# main.net
KiCad netlist of a schematic drawn in EAGLE
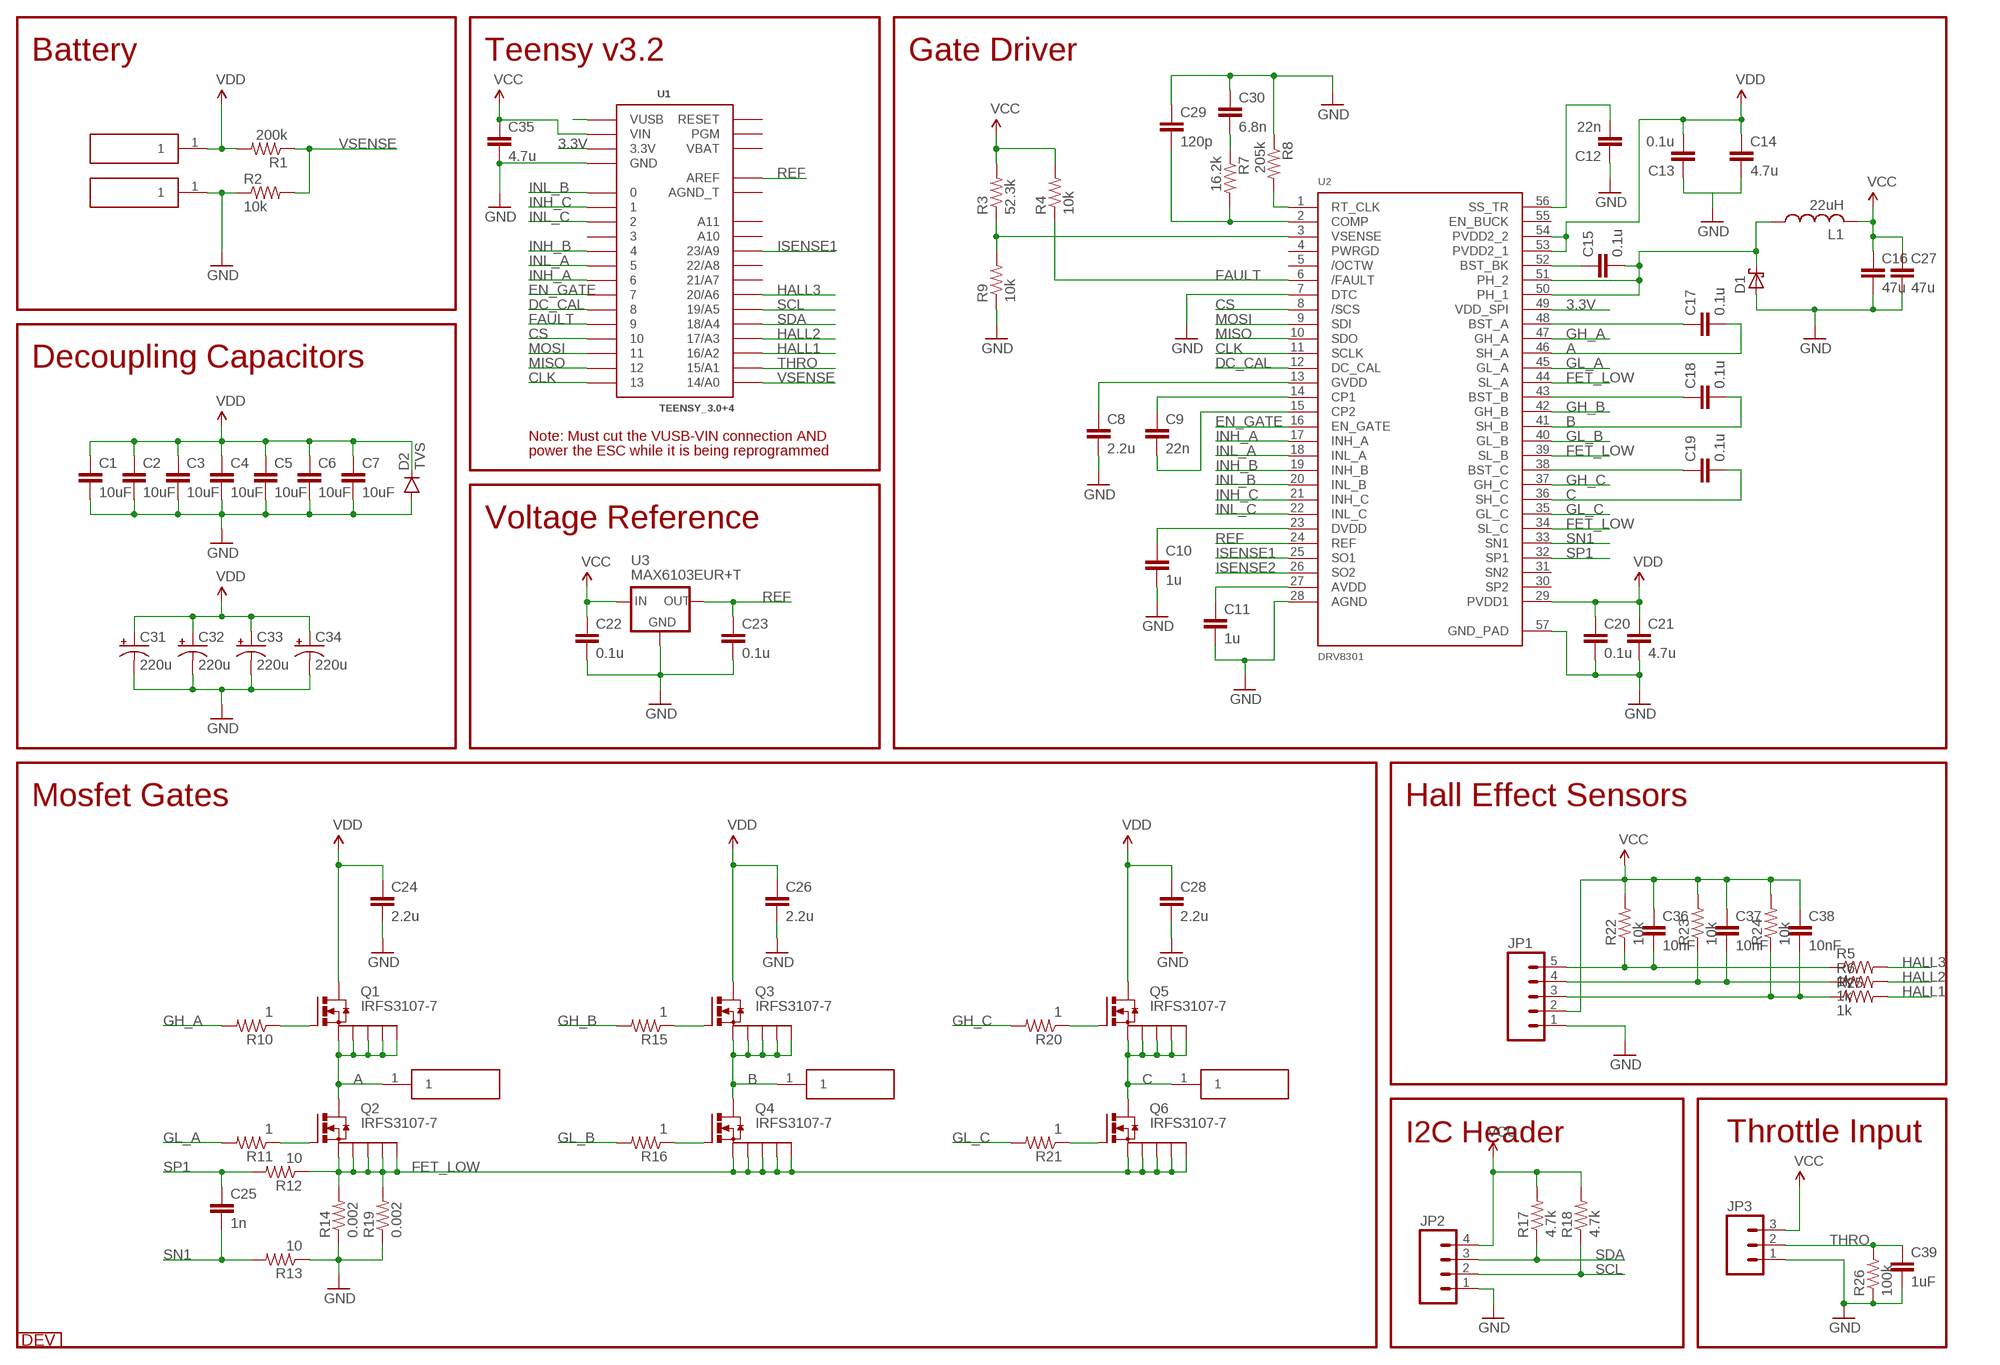
[diagram p0: schematic, sheet 1]

(export (version "E")
  (design (tool "Eeschema 10.0.6"))
  (components
    (comp (ref "C1")
      (value "10uF")
      (footprint "eagle-import:1206")
      (libsource (lib "eagle-import") (part "CAP1206"))
    )
    (comp (ref "C2")
      (value "10uF")
      (footprint "eagle-import:1206")
      (libsource (lib "eagle-import") (part "CAP1206"))
    )
    (comp (ref "C3")
      (value "10uF")
      (footprint "eagle-import:1206")
      (libsource (lib "eagle-import") (part "CAP1206"))
    )
    (comp (ref "C4")
      (value "10uF")
      (footprint "eagle-import:1206")
      (libsource (lib "eagle-import") (part "CAP1206"))
    )
    (comp (ref "C5")
      (value "10uF")
      (footprint "eagle-import:1206")
      (libsource (lib "eagle-import") (part "CAP1206"))
    )
    (comp (ref "C6")
      (value "10uF")
      (footprint "eagle-import:1206")
      (libsource (lib "eagle-import") (part "CAP1206"))
    )
    (comp (ref "C7")
      (value "10uF")
      (footprint "eagle-import:1206")
      (libsource (lib "eagle-import") (part "CAP1206"))
    )
    (comp (ref "C8")
      (value "2.2u")
      (footprint "eagle-import:0603-CAP")
      (libsource (lib "eagle-import") (part "CAP0603-CAP"))
    )
    (comp (ref "C9")
      (value "22n")
      (footprint "eagle-import:0603-CAP")
      (libsource (lib "eagle-import") (part "CAP0603-CAP"))
    )
    (comp (ref "C10")
      (value "1u")
      (footprint "eagle-import:0603-CAP")
      (libsource (lib "eagle-import") (part "CAP0603-CAP"))
    )
    (comp (ref "C11")
      (value "1u")
      (footprint "eagle-import:0603-CAP")
      (libsource (lib "eagle-import") (part "CAP0603-CAP"))
    )
    (comp (ref "C12")
      (value "22n")
      (footprint "eagle-import:0603-CAP")
      (libsource (lib "eagle-import") (part "CAP0603-CAP"))
    )
    (comp (ref "C13")
      (value "0.1u")
      (footprint "eagle-import:0603-CAP")
      (libsource (lib "eagle-import") (part "CAP0603-CAP"))
    )
    (comp (ref "C14")
      (value "4.7u")
      (footprint "eagle-import:0805")
      (libsource (lib "eagle-import") (part "CAP0805"))
    )
    (comp (ref "C15")
      (value "0.1u")
      (footprint "eagle-import:0603-CAP")
      (libsource (lib "eagle-import") (part "CAP0603-CAP"))
    )
    (comp (ref "C16")
      (value "47u")
      (footprint "eagle-import:0805")
      (libsource (lib "eagle-import") (part "CAP0805"))
    )
    (comp (ref "C17")
      (value "0.1u")
      (footprint "eagle-import:0603-CAP")
      (libsource (lib "eagle-import") (part "CAP0603-CAP"))
    )
    (comp (ref "C18")
      (value "0.1u")
      (footprint "eagle-import:0603-CAP")
      (libsource (lib "eagle-import") (part "CAP0603-CAP"))
    )
    (comp (ref "C19")
      (value "0.1u")
      (footprint "eagle-import:0603-CAP")
      (libsource (lib "eagle-import") (part "CAP0603-CAP"))
    )
    (comp (ref "C20")
      (value "0.1u")
      (footprint "eagle-import:0603-CAP")
      (libsource (lib "eagle-import") (part "CAP0603-CAP"))
    )
    (comp (ref "C21")
      (value "4.7u")
      (footprint "eagle-import:0805")
      (libsource (lib "eagle-import") (part "CAP0805"))
    )
    (comp (ref "C22")
      (value "0.1u")
      (footprint "eagle-import:0603-CAP")
      (libsource (lib "eagle-import") (part "CAP0603-CAP"))
    )
    (comp (ref "C23")
      (value "0.1u")
      (footprint "eagle-import:0603-CAP")
      (libsource (lib "eagle-import") (part "CAP0603-CAP"))
    )
    (comp (ref "C24")
      (value "2.2u")
      (footprint "eagle-import:1206")
      (libsource (lib "eagle-import") (part "CAP1206"))
    )
    (comp (ref "C25")
      (value "1n")
      (footprint "eagle-import:0603-CAP")
      (libsource (lib "eagle-import") (part "CAP0603-CAP"))
    )
    (comp (ref "C26")
      (value "2.2u")
      (footprint "eagle-import:1206")
      (libsource (lib "eagle-import") (part "CAP1206"))
    )
    (comp (ref "C27")
      (value "47u")
      (footprint "eagle-import:0805")
      (libsource (lib "eagle-import") (part "CAP0805"))
    )
    (comp (ref "C28")
      (value "2.2u")
      (footprint "eagle-import:1206")
      (libsource (lib "eagle-import") (part "CAP1206"))
    )
    (comp (ref "C29")
      (value "120p")
      (footprint "eagle-import:0603-CAP")
      (libsource (lib "eagle-import") (part "CAP0603-CAP"))
    )
    (comp (ref "C30")
      (value "6.8n")
      (footprint "eagle-import:0603-CAP")
      (libsource (lib "eagle-import") (part "CAP0603-CAP"))
    )
    (comp (ref "C31")
      (value "220u")
      (footprint "eagle-import:E3,5-8")
      (libsource (lib "eagle-import") (part "CPOL-USE3.5-8"))
    )
    (comp (ref "C32")
      (value "220u")
      (footprint "eagle-import:E3,5-8")
      (libsource (lib "eagle-import") (part "CPOL-USE3.5-8"))
    )
    (comp (ref "C33")
      (value "220u")
      (footprint "eagle-import:E3,5-8")
      (libsource (lib "eagle-import") (part "CPOL-USE3.5-8"))
    )
    (comp (ref "C34")
      (value "220u")
      (footprint "eagle-import:E3,5-8")
      (libsource (lib "eagle-import") (part "CPOL-USE3.5-8"))
    )
    (comp (ref "C35")
      (value "4.7u")
      (footprint "eagle-import:0603-CAP")
      (libsource (lib "eagle-import") (part "CAP0603-CAP"))
    )
    (comp (ref "C36")
      (value "10nF")
      (footprint "eagle-import:0603-CAP")
      (libsource (lib "eagle-import") (part "SparkFun-Passives_CAP0603-CAP"))
    )
    (comp (ref "C37")
      (value "10nF")
      (footprint "eagle-import:0603-CAP")
      (libsource (lib "eagle-import") (part "SparkFun-Passives_CAP0603-CAP"))
    )
    (comp (ref "C38")
      (value "10nF")
      (footprint "eagle-import:0603-CAP")
      (libsource (lib "eagle-import") (part "SparkFun-Passives_CAP0603-CAP"))
    )
    (comp (ref "C39")
      (value "1uF")
      (footprint "eagle-import:0603-CAP")
      (libsource (lib "eagle-import") (part "SparkFun-Passives_CAP0603-CAP"))
    )
    (comp (ref "D1")
      (value "SCHOTTKY_SMA")
      (footprint "eagle-import:SMA")
      (libsource (lib "eagle-import") (part "SCHOTTKY_SMA"))
    )
    (comp (ref "D2")
      (value "TVS")
      (footprint "eagle-import:SMC")
      (libsource (lib "eagle-import") (part "DIODEES3J"))
    )
    (comp (ref "J1")
      (value "0.125_PAD")
      (footprint "eagle-import:0.125_PAD")
      (libsource (lib "eagle-import") (part "0.125_PAD"))
    )
    (comp (ref "J2")
      (value "0.125_PAD")
      (footprint "eagle-import:0.125_PAD")
      (libsource (lib "eagle-import") (part "0.125_PAD"))
    )
    (comp (ref "J3")
      (value "0.125_PAD")
      (footprint "eagle-import:0.125_PAD")
      (libsource (lib "eagle-import") (part "0.125_PAD"))
    )
    (comp (ref "J4")
      (value "0.125_PAD")
      (footprint "eagle-import:0.125_PAD")
      (libsource (lib "eagle-import") (part "0.125_PAD"))
    )
    (comp (ref "J5")
      (value "0.125_PAD")
      (footprint "eagle-import:0.125_PAD")
      (libsource (lib "eagle-import") (part "0.125_PAD"))
    )
    (comp (ref "JP1")
      (value "M05PTH")
      (footprint "eagle-import:1X05")
      (libsource (lib "eagle-import") (part "M05PTH"))
    )
    (comp (ref "JP2")
      (value "M04PTH")
      (footprint "eagle-import:1X04")
      (libsource (lib "eagle-import") (part "M04PTH"))
    )
    (comp (ref "JP3")
      (value "M03PTH")
      (footprint "eagle-import:1X03")
      (libsource (lib "eagle-import") (part "M03PTH"))
    )
    (comp (ref "L1")
      (value "22uH")
      (footprint "eagle-import:L5650M")
      (libsource (lib "eagle-import") (part "L-USL5650M"))
    )
    (comp (ref "Q1")
      (value "IRFS3107-7")
      (footprint "eagle-import:D2PAK-7")
      (libsource (lib "eagle-import") (part "IRFS3107-7"))
    )
    (comp (ref "Q2")
      (value "IRFS3107-7")
      (footprint "eagle-import:D2PAK-7")
      (libsource (lib "eagle-import") (part "IRFS3107-7"))
    )
    (comp (ref "Q3")
      (value "IRFS3107-7")
      (footprint "eagle-import:D2PAK-7")
      (libsource (lib "eagle-import") (part "IRFS3107-7"))
    )
    (comp (ref "Q4")
      (value "IRFS3107-7")
      (footprint "eagle-import:D2PAK-7")
      (libsource (lib "eagle-import") (part "IRFS3107-7"))
    )
    (comp (ref "Q5")
      (value "IRFS3107-7")
      (footprint "eagle-import:D2PAK-7")
      (libsource (lib "eagle-import") (part "IRFS3107-7"))
    )
    (comp (ref "Q6")
      (value "IRFS3107-7")
      (footprint "eagle-import:D2PAK-7")
      (libsource (lib "eagle-import") (part "IRFS3107-7"))
    )
    (comp (ref "R1")
      (value "200k")
      (footprint "eagle-import:0603-RES")
      (libsource (lib "eagle-import") (part "RESISTOR0603"))
    )
    (comp (ref "R2")
      (value "10k")
      (footprint "eagle-import:0603-RES")
      (libsource (lib "eagle-import") (part "RESISTOR0603"))
    )
    (comp (ref "R3")
      (value "52.3k")
      (footprint "eagle-import:0603-RES")
      (libsource (lib "eagle-import") (part "RESISTOR0603"))
    )
    (comp (ref "R4")
      (value "10k")
      (footprint "eagle-import:0603-RES")
      (libsource (lib "eagle-import") (part "RESISTOR0603"))
    )
    (comp (ref "R5")
      (value "1k")
      (footprint "eagle-import:0603-RES")
      (libsource (lib "eagle-import") (part "RESISTOR0603-RES"))
    )
    (comp (ref "R6")
      (value "1k")
      (footprint "eagle-import:0603-RES")
      (libsource (lib "eagle-import") (part "RESISTOR0603-RES"))
    )
    (comp (ref "R7")
      (value "16.2k")
      (footprint "eagle-import:0603-RES")
      (libsource (lib "eagle-import") (part "RESISTOR0603"))
    )
    (comp (ref "R8")
      (value "205k")
      (footprint "eagle-import:0603-RES")
      (libsource (lib "eagle-import") (part "RESISTOR0603"))
    )
    (comp (ref "R9")
      (value "10k")
      (footprint "eagle-import:0603-RES")
      (libsource (lib "eagle-import") (part "RESISTOR0603"))
    )
    (comp (ref "R10")
      (value "1")
      (footprint "eagle-import:0603-RES")
      (libsource (lib "eagle-import") (part "RESISTOR0603"))
    )
    (comp (ref "R11")
      (value "1")
      (footprint "eagle-import:0603-RES")
      (libsource (lib "eagle-import") (part "RESISTOR0603"))
    )
    (comp (ref "R12")
      (value "10")
      (footprint "eagle-import:0603-RES")
      (libsource (lib "eagle-import") (part "RESISTOR0603"))
    )
    (comp (ref "R13")
      (value "10")
      (footprint "eagle-import:0603-RES")
      (libsource (lib "eagle-import") (part "RESISTOR0603"))
    )
    (comp (ref "R14")
      (value "0.002")
      (footprint "eagle-import:R2512")
      (libsource (lib "eagle-import") (part "SparkFun-Resistors_RESISTOR2512"))
    )
    (comp (ref "R15")
      (value "1")
      (footprint "eagle-import:0603-RES")
      (libsource (lib "eagle-import") (part "RESISTOR0603"))
    )
    (comp (ref "R16")
      (value "1")
      (footprint "eagle-import:0603-RES")
      (libsource (lib "eagle-import") (part "RESISTOR0603"))
    )
    (comp (ref "R17")
      (value "4.7k")
      (footprint "eagle-import:0603-RES")
      (libsource (lib "eagle-import") (part "RESISTOR0603-RES"))
    )
    (comp (ref "R18")
      (value "4.7k")
      (footprint "eagle-import:0603-RES")
      (libsource (lib "eagle-import") (part "RESISTOR0603-RES"))
    )
    (comp (ref "R19")
      (value "0.002")
      (footprint "eagle-import:R2512")
      (libsource (lib "eagle-import") (part "SparkFun-Resistors_RESISTOR2512"))
    )
    (comp (ref "R20")
      (value "1")
      (footprint "eagle-import:0603-RES")
      (libsource (lib "eagle-import") (part "RESISTOR0603"))
    )
    (comp (ref "R21")
      (value "1")
      (footprint "eagle-import:0603-RES")
      (libsource (lib "eagle-import") (part "RESISTOR0603"))
    )
    (comp (ref "R22")
      (value "10k")
      (footprint "eagle-import:0603-RES")
      (libsource (lib "eagle-import") (part "RESISTOR0603"))
    )
    (comp (ref "R23")
      (value "10k")
      (footprint "eagle-import:0603-RES")
      (libsource (lib "eagle-import") (part "RESISTOR0603"))
    )
    (comp (ref "R24")
      (value "10k")
      (footprint "eagle-import:0603-RES")
      (libsource (lib "eagle-import") (part "RESISTOR0603"))
    )
    (comp (ref "R25")
      (value "1k")
      (footprint "eagle-import:0603-RES")
      (libsource (lib "eagle-import") (part "RESISTOR0603-RES"))
    )
    (comp (ref "R26")
      (value "100k")
      (footprint "eagle-import:0603-RES")
      (libsource (lib "eagle-import") (part "RESISTOR0603-RES"))
    )
    (comp (ref "U$16")
      (value "DEV")
      (footprint "eagle-import:DEV")
      (libsource (lib "eagle-import") (part "DEV"))
    )
    (comp (ref "U1")
      (value "TEENSY_3.0+4")
      (footprint "eagle-import:TEENSY_3.0+4")
      (libsource (lib "eagle-import") (part "TEENSY_3.0+4"))
    )
    (comp (ref "U2")
      (value "DRV8301")
      (footprint "eagle-import:DRV8301")
      (libsource (lib "eagle-import") (part "DRV8301"))
    )
    (comp (ref "U3")
      (value "MAX6103EUR+T")
      (footprint "eagle-import:SOT23-3")
      (libsource (lib "eagle-import") (part "MAX6103EUR+T"))
    )
  )
  (nets
    (net (code "1") (name "/3.3V") (class "Default")
      (node (ref "U1") (pin "3.3V") (pinfunction "3.3V_3.3V") (pintype "power_in"))
      (node (ref "U1") (pin "3.3V1") (pinfunction "3.3V_3.3V1") (pintype "power_in"))
      (node (ref "U2") (pin "49") (pinfunction "VDD_SPI_49") (pintype "bidirectional"))
    )
    (net (code "2") (name "/A") (class "Default")
      (node (ref "C17") (pin "2") (pinfunction "2_2") (pintype "passive"))
      (node (ref "J3") (pin "1") (pinfunction "1_1") (pintype "bidirectional"))
      (node (ref "Q1") (pin "S") (pinfunction "S_S") (pintype "passive"))
      (node (ref "Q1") (pin "S1") (pinfunction "S1_S1") (pintype "passive"))
      (node (ref "Q1") (pin "S2") (pinfunction "S2_S2") (pintype "passive"))
      (node (ref "Q1") (pin "S3") (pinfunction "S3_S3") (pintype "passive"))
      (node (ref "Q1") (pin "S4") (pinfunction "S4_S4") (pintype "passive"))
      (node (ref "Q2") (pin "D") (pinfunction "D_D") (pintype "passive"))
      (node (ref "U2") (pin "46") (pinfunction "SH_A_46") (pintype "bidirectional"))
    )
    (net (code "3") (name "/AGND_T") (class "Default")
      (node (ref "U1") (pin "AGND_T") (pinfunction "AGND_T_AGND_T") (pintype "power_in"))
    )
    (net (code "4") (name "/B") (class "Default")
      (node (ref "C18") (pin "2") (pinfunction "2_2") (pintype "passive"))
      (node (ref "J4") (pin "1") (pinfunction "1_1") (pintype "bidirectional"))
      (node (ref "Q3") (pin "S") (pinfunction "S_S") (pintype "passive"))
      (node (ref "Q3") (pin "S1") (pinfunction "S1_S1") (pintype "passive"))
      (node (ref "Q3") (pin "S2") (pinfunction "S2_S2") (pintype "passive"))
      (node (ref "Q3") (pin "S3") (pinfunction "S3_S3") (pintype "passive"))
      (node (ref "Q3") (pin "S4") (pinfunction "S4_S4") (pintype "passive"))
      (node (ref "Q4") (pin "D") (pinfunction "D_D") (pintype "passive"))
      (node (ref "U2") (pin "41") (pinfunction "SH_B_41") (pintype "bidirectional"))
    )
    (net (code "5") (name "/C") (class "Default")
      (node (ref "C19") (pin "2") (pinfunction "2_2") (pintype "passive"))
      (node (ref "J5") (pin "1") (pinfunction "1_1") (pintype "bidirectional"))
      (node (ref "Q5") (pin "S") (pinfunction "S_S") (pintype "passive"))
      (node (ref "Q5") (pin "S1") (pinfunction "S1_S1") (pintype "passive"))
      (node (ref "Q5") (pin "S2") (pinfunction "S2_S2") (pintype "passive"))
      (node (ref "Q5") (pin "S3") (pinfunction "S3_S3") (pintype "passive"))
      (node (ref "Q5") (pin "S4") (pinfunction "S4_S4") (pintype "passive"))
      (node (ref "Q6") (pin "D") (pinfunction "D_D") (pintype "passive"))
      (node (ref "U2") (pin "36") (pinfunction "SH_C_36") (pintype "bidirectional"))
    )
    (net (code "6") (name "/CLK") (class "Default")
      (node (ref "U1") (pin "13") (pinfunction "13_13") (pintype "bidirectional"))
      (node (ref "U2") (pin "11") (pinfunction "SCLK_11") (pintype "bidirectional"))
    )
    (net (code "7") (name "/CS") (class "Default")
      (node (ref "U1") (pin "10") (pinfunction "10_10") (pintype "bidirectional"))
      (node (ref "U2") (pin "8") (pinfunction "/SCS_8") (pintype "bidirectional"))
    )
    (net (code "8") (name "/DC_CAL") (class "Default")
      (node (ref "U1") (pin "8") (pinfunction "8_8") (pintype "bidirectional"))
      (node (ref "U2") (pin "12") (pinfunction "DC_CAL_12") (pintype "bidirectional"))
    )
    (net (code "9") (name "/EN_GATE") (class "Default")
      (node (ref "U1") (pin "7") (pinfunction "7_7") (pintype "bidirectional"))
      (node (ref "U2") (pin "16") (pinfunction "EN_GATE_16") (pintype "bidirectional"))
    )
    (net (code "10") (name "/FAULT") (class "Default")
      (node (ref "R4") (pin "1") (pinfunction "1_1") (pintype "passive"))
      (node (ref "U1") (pin "9") (pinfunction "9_9") (pintype "bidirectional"))
      (node (ref "U2") (pin "6") (pinfunction "/FAULT_6") (pintype "bidirectional"))
    )
    (net (code "11") (name "/FET_LOW") (class "Default")
      (node (ref "Q2") (pin "S") (pinfunction "S_S") (pintype "passive"))
      (node (ref "Q2") (pin "S1") (pinfunction "S1_S1") (pintype "passive"))
      (node (ref "Q2") (pin "S2") (pinfunction "S2_S2") (pintype "passive"))
      (node (ref "Q2") (pin "S3") (pinfunction "S3_S3") (pintype "passive"))
      (node (ref "Q2") (pin "S4") (pinfunction "S4_S4") (pintype "passive"))
      (node (ref "Q4") (pin "S") (pinfunction "S_S") (pintype "passive"))
      (node (ref "Q4") (pin "S1") (pinfunction "S1_S1") (pintype "passive"))
      (node (ref "Q4") (pin "S2") (pinfunction "S2_S2") (pintype "passive"))
      (node (ref "Q4") (pin "S3") (pinfunction "S3_S3") (pintype "passive"))
      (node (ref "Q4") (pin "S4") (pinfunction "S4_S4") (pintype "passive"))
      (node (ref "Q6") (pin "S") (pinfunction "S_S") (pintype "passive"))
      (node (ref "Q6") (pin "S1") (pinfunction "S1_S1") (pintype "passive"))
      (node (ref "Q6") (pin "S2") (pinfunction "S2_S2") (pintype "passive"))
      (node (ref "Q6") (pin "S3") (pinfunction "S3_S3") (pintype "passive"))
      (node (ref "Q6") (pin "S4") (pinfunction "S4_S4") (pintype "passive"))
      (node (ref "R12") (pin "1") (pinfunction "1_1") (pintype "passive"))
      (node (ref "R14") (pin "2") (pinfunction "2_2") (pintype "passive"))
      (node (ref "R19") (pin "2") (pinfunction "2_2") (pintype "passive"))
      (node (ref "U2") (pin "34") (pinfunction "SL_C_34") (pintype "bidirectional"))
      (node (ref "U2") (pin "39") (pinfunction "SL_B_39") (pintype "bidirectional"))
      (node (ref "U2") (pin "44") (pinfunction "SL_A_44") (pintype "bidirectional"))
    )
    (net (code "12") (name "/GH_A") (class "Default")
      (node (ref "R10") (pin "2") (pinfunction "2_2") (pintype "passive"))
      (node (ref "U2") (pin "47") (pinfunction "GH_A_47") (pintype "bidirectional"))
    )
    (net (code "13") (name "/GH_B") (class "Default")
      (node (ref "R15") (pin "2") (pinfunction "2_2") (pintype "passive"))
      (node (ref "U2") (pin "42") (pinfunction "GH_B_42") (pintype "bidirectional"))
    )
    (net (code "14") (name "/GH_C") (class "Default")
      (node (ref "R20") (pin "2") (pinfunction "2_2") (pintype "passive"))
      (node (ref "U2") (pin "37") (pinfunction "GH_C_37") (pintype "bidirectional"))
    )
    (net (code "15") (name "/GL_A") (class "Default")
      (node (ref "R11") (pin "2") (pinfunction "2_2") (pintype "passive"))
      (node (ref "U2") (pin "45") (pinfunction "GL_A_45") (pintype "bidirectional"))
    )
    (net (code "16") (name "/GL_B") (class "Default")
      (node (ref "R16") (pin "2") (pinfunction "2_2") (pintype "passive"))
      (node (ref "U2") (pin "40") (pinfunction "GL_B_40") (pintype "bidirectional"))
    )
    (net (code "17") (name "/GL_C") (class "Default")
      (node (ref "R21") (pin "2") (pinfunction "2_2") (pintype "passive"))
      (node (ref "U2") (pin "35") (pinfunction "GL_C_35") (pintype "bidirectional"))
    )
    (net (code "18") (name "/HALL1") (class "Default")
      (node (ref "R25") (pin "2") (pinfunction "2_2") (pintype "passive"))
      (node (ref "U1") (pin "16/A2") (pinfunction "16/A2_16/A2") (pintype "bidirectional"))
    )
    (net (code "19") (name "/HALL2") (class "Default")
      (node (ref "R6") (pin "2") (pinfunction "2_2") (pintype "passive"))
      (node (ref "U1") (pin "17/A3") (pinfunction "17/A3_17/A3") (pintype "bidirectional"))
    )
    (net (code "20") (name "/HALL3") (class "Default")
      (node (ref "R5") (pin "2") (pinfunction "2_2") (pintype "passive"))
      (node (ref "U1") (pin "20/A6") (pinfunction "20/A6_20/A6") (pintype "bidirectional"))
    )
    (net (code "21") (name "/INH_A") (class "Default")
      (node (ref "U1") (pin "6") (pinfunction "6_6") (pintype "bidirectional"))
      (node (ref "U2") (pin "17") (pinfunction "INH_A_17") (pintype "bidirectional"))
    )
    (net (code "22") (name "/INH_B") (class "Default")
      (node (ref "U1") (pin "4") (pinfunction "4_4") (pintype "bidirectional"))
      (node (ref "U2") (pin "19") (pinfunction "INH_B_19") (pintype "bidirectional"))
    )
    (net (code "23") (name "/INH_C") (class "Default")
      (node (ref "U1") (pin "1") (pinfunction "1_1") (pintype "bidirectional"))
      (node (ref "U2") (pin "21") (pinfunction "INH_C_21") (pintype "bidirectional"))
    )
    (net (code "24") (name "/INL_A") (class "Default")
      (node (ref "U1") (pin "5") (pinfunction "5_5") (pintype "bidirectional"))
      (node (ref "U2") (pin "18") (pinfunction "INL_A_18") (pintype "bidirectional"))
    )
    (net (code "25") (name "/INL_B") (class "Default")
      (node (ref "U1") (pin "0") (pinfunction "0_0") (pintype "bidirectional"))
      (node (ref "U2") (pin "20") (pinfunction "INL_B_20") (pintype "bidirectional"))
    )
    (net (code "26") (name "/INL_C") (class "Default")
      (node (ref "U1") (pin "2") (pinfunction "2_2") (pintype "bidirectional"))
      (node (ref "U2") (pin "22") (pinfunction "INL_C_22") (pintype "bidirectional"))
    )
    (net (code "27") (name "/ISENSE1") (class "Default")
      (node (ref "U1") (pin "23/A9") (pinfunction "23/A9_23/A9") (pintype "bidirectional"))
      (node (ref "U2") (pin "25") (pinfunction "SO1_25") (pintype "bidirectional"))
    )
    (net (code "28") (name "/ISENSE2") (class "Default")
      (node (ref "U2") (pin "26") (pinfunction "SO2_26") (pintype "bidirectional"))
    )
    (net (code "29") (name "/MISO") (class "Default")
      (node (ref "U1") (pin "12") (pinfunction "12_12") (pintype "bidirectional"))
      (node (ref "U2") (pin "10") (pinfunction "SDO_10") (pintype "bidirectional"))
    )
    (net (code "30") (name "/MOSI") (class "Default")
      (node (ref "U1") (pin "11") (pinfunction "11_11") (pintype "bidirectional"))
      (node (ref "U2") (pin "9") (pinfunction "SDI_9") (pintype "bidirectional"))
    )
    (net (code "31") (name "/REF") (class "Default")
      (node (ref "C23") (pin "1") (pinfunction "1_1") (pintype "passive"))
      (node (ref "U1") (pin "AREF") (pinfunction "AREF_AREF") (pintype "power_in"))
      (node (ref "U2") (pin "24") (pinfunction "REF_24") (pintype "bidirectional"))
      (node (ref "U3") (pin "2") (pinfunction "OUT_2") (pintype "output"))
    )
    (net (code "32") (name "/SCL") (class "Default")
      (node (ref "JP2") (pin "2") (pinfunction "2_2") (pintype "passive"))
      (node (ref "R18") (pin "1") (pinfunction "1_1") (pintype "passive"))
      (node (ref "U1") (pin "19/A5") (pinfunction "19/A5_19/A5") (pintype "bidirectional"))
    )
    (net (code "33") (name "/SDA") (class "Default")
      (node (ref "JP2") (pin "3") (pinfunction "3_3") (pintype "passive"))
      (node (ref "R17") (pin "1") (pinfunction "1_1") (pintype "passive"))
      (node (ref "U1") (pin "18/A4") (pinfunction "18/A4_18/A4") (pintype "bidirectional"))
    )
    (net (code "34") (name "/SN1") (class "Default")
      (node (ref "C25") (pin "2") (pinfunction "2_2") (pintype "passive"))
      (node (ref "R13") (pin "2") (pinfunction "2_2") (pintype "passive"))
      (node (ref "U2") (pin "33") (pinfunction "SN1_33") (pintype "bidirectional"))
    )
    (net (code "35") (name "/SP1") (class "Default")
      (node (ref "C25") (pin "1") (pinfunction "1_1") (pintype "passive"))
      (node (ref "R12") (pin "2") (pinfunction "2_2") (pintype "passive"))
      (node (ref "U2") (pin "32") (pinfunction "SP1_32") (pintype "bidirectional"))
    )
    (net (code "36") (name "/THRO") (class "Default")
      (node (ref "C39") (pin "1") (pinfunction "1_1") (pintype "passive"))
      (node (ref "JP3") (pin "2") (pinfunction "2_2") (pintype "passive"))
      (node (ref "R26") (pin "2") (pinfunction "2_2") (pintype "passive"))
      (node (ref "U1") (pin "15/A1") (pinfunction "15/A1_15/A1") (pintype "bidirectional"))
    )
    (net (code "37") (name "/VBAT") (class "Default")
      (node (ref "U1") (pin "VBAT") (pinfunction "VBAT_VBAT") (pintype "power_in"))
    )
    (net (code "38") (name "/VSENSE") (class "Default")
      (node (ref "R1") (pin "1") (pinfunction "1_1") (pintype "passive"))
      (node (ref "R2") (pin "2") (pinfunction "2_2") (pintype "passive"))
      (node (ref "U1") (pin "14/A0") (pinfunction "14/A0_14/A0") (pintype "bidirectional"))
    )
    (net (code "39") (name "GND") (class "Default")
      (node (ref "C1") (pin "2") (pinfunction "2_2") (pintype "passive"))
      (node (ref "C10") (pin "2") (pinfunction "2_2") (pintype "passive"))
      (node (ref "C11") (pin "2") (pinfunction "2_2") (pintype "passive"))
      (node (ref "C12") (pin "1") (pinfunction "1_1") (pintype "passive"))
      (node (ref "C13") (pin "1") (pinfunction "1_1") (pintype "passive"))
      (node (ref "C14") (pin "2") (pinfunction "2_2") (pintype "passive"))
      (node (ref "C16") (pin "2") (pinfunction "2_2") (pintype "passive"))
      (node (ref "C2") (pin "2") (pinfunction "2_2") (pintype "passive"))
      (node (ref "C20") (pin "2") (pinfunction "2_2") (pintype "passive"))
      (node (ref "C21") (pin "2") (pinfunction "2_2") (pintype "passive"))
      (node (ref "C22") (pin "2") (pinfunction "2_2") (pintype "passive"))
      (node (ref "C23") (pin "2") (pinfunction "2_2") (pintype "passive"))
      (node (ref "C24") (pin "2") (pinfunction "2_2") (pintype "passive"))
      (node (ref "C26") (pin "2") (pinfunction "2_2") (pintype "passive"))
      (node (ref "C27") (pin "2") (pinfunction "2_2") (pintype "passive"))
      (node (ref "C28") (pin "2") (pinfunction "2_2") (pintype "passive"))
      (node (ref "C29") (pin "1") (pinfunction "1_1") (pintype "passive"))
      (node (ref "C3") (pin "2") (pinfunction "2_2") (pintype "passive"))
      (node (ref "C30") (pin "1") (pinfunction "1_1") (pintype "passive"))
      (node (ref "C31") (pin "-") (pinfunction "-_-") (pintype "passive"))
      (node (ref "C32") (pin "-") (pinfunction "-_-") (pintype "passive"))
      (node (ref "C33") (pin "-") (pinfunction "-_-") (pintype "passive"))
      (node (ref "C34") (pin "-") (pinfunction "-_-") (pintype "passive"))
      (node (ref "C35") (pin "2") (pinfunction "2_2") (pintype "passive"))
      (node (ref "C39") (pin "2") (pinfunction "2_2") (pintype "passive"))
      (node (ref "C4") (pin "2") (pinfunction "2_2") (pintype "passive"))
      (node (ref "C5") (pin "2") (pinfunction "2_2") (pintype "passive"))
      (node (ref "C6") (pin "2") (pinfunction "2_2") (pintype "passive"))
      (node (ref "C7") (pin "2") (pinfunction "2_2") (pintype "passive"))
      (node (ref "C8") (pin "2") (pinfunction "2_2") (pintype "passive"))
      (node (ref "D1") (pin "A") (pinfunction "A_A") (pintype "passive"))
      (node (ref "D2") (pin "A") (pinfunction "A_A") (pintype "passive"))
      (node (ref "J2") (pin "1") (pinfunction "1_1") (pintype "bidirectional"))
      (node (ref "JP1") (pin "1") (pinfunction "1_1") (pintype "passive"))
      (node (ref "JP2") (pin "1") (pinfunction "1_1") (pintype "passive"))
      (node (ref "JP3") (pin "1") (pinfunction "1_1") (pintype "passive"))
      (node (ref "R13") (pin "1") (pinfunction "1_1") (pintype "passive"))
      (node (ref "R14") (pin "1") (pinfunction "1_1") (pintype "passive"))
      (node (ref "R19") (pin "1") (pinfunction "1_1") (pintype "passive"))
      (node (ref "R2") (pin "1") (pinfunction "1_1") (pintype "passive"))
      (node (ref "R26") (pin "1") (pinfunction "1_1") (pintype "passive"))
      (node (ref "R8") (pin "1") (pinfunction "1_1") (pintype "passive"))
      (node (ref "R9") (pin "1") (pinfunction "1_1") (pintype "passive"))
      (node (ref "U1") (pin "GND") (pinfunction "GND_GND") (pintype "power_in"))
      (node (ref "U1") (pin "GND1") (pinfunction "GND_GND1") (pintype "power_in"))
      (node (ref "U2") (pin "28") (pinfunction "AGND_28") (pintype "bidirectional"))
      (node (ref "U2") (pin "57") (pinfunction "GND_PAD_57") (pintype "bidirectional"))
      (node (ref "U2") (pin "7") (pinfunction "DTC_7") (pintype "bidirectional"))
      (node (ref "U3") (pin "3") (pinfunction "GND_3") (pintype "input"))
    )
    (net (code "40") (name "Net-(C30-Pad2)") (class "Default")
      (node (ref "C30") (pin "2") (pinfunction "2_2") (pintype "passive"))
      (node (ref "R7") (pin "1") (pinfunction "1_1") (pintype "passive"))
    )
    (net (code "41") (name "Net-(C36-Pad2)") (class "Default")
      (node (ref "C36") (pin "2") (pinfunction "2_2") (pintype "passive"))
      (node (ref "JP1") (pin "5") (pinfunction "5_5") (pintype "passive"))
      (node (ref "R22") (pin "1") (pinfunction "1_1") (pintype "passive"))
      (node (ref "R5") (pin "1") (pinfunction "1_1") (pintype "passive"))
    )
    (net (code "42") (name "Net-(C37-Pad2)") (class "Default")
      (node (ref "C37") (pin "2") (pinfunction "2_2") (pintype "passive"))
      (node (ref "JP1") (pin "4") (pinfunction "4_4") (pintype "passive"))
      (node (ref "R23") (pin "1") (pinfunction "1_1") (pintype "passive"))
      (node (ref "R6") (pin "1") (pinfunction "1_1") (pintype "passive"))
    )
    (net (code "43") (name "Net-(C38-Pad2)") (class "Default")
      (node (ref "C38") (pin "2") (pinfunction "2_2") (pintype "passive"))
      (node (ref "JP1") (pin "3") (pinfunction "3_3") (pintype "passive"))
      (node (ref "R24") (pin "1") (pinfunction "1_1") (pintype "passive"))
      (node (ref "R25") (pin "1") (pinfunction "1_1") (pintype "passive"))
    )
    (net (code "44") (name "Net-(Q1-PadG)") (class "Default")
      (node (ref "Q1") (pin "G") (pinfunction "G_G") (pintype "passive"))
      (node (ref "R10") (pin "1") (pinfunction "1_1") (pintype "passive"))
    )
    (net (code "45") (name "Net-(Q2-PadG)") (class "Default")
      (node (ref "Q2") (pin "G") (pinfunction "G_G") (pintype "passive"))
      (node (ref "R11") (pin "1") (pinfunction "1_1") (pintype "passive"))
    )
    (net (code "46") (name "Net-(Q3-PadG)") (class "Default")
      (node (ref "Q3") (pin "G") (pinfunction "G_G") (pintype "passive"))
      (node (ref "R15") (pin "1") (pinfunction "1_1") (pintype "passive"))
    )
    (net (code "47") (name "Net-(Q4-PadG)") (class "Default")
      (node (ref "Q4") (pin "G") (pinfunction "G_G") (pintype "passive"))
      (node (ref "R16") (pin "1") (pinfunction "1_1") (pintype "passive"))
    )
    (net (code "48") (name "Net-(Q5-PadG)") (class "Default")
      (node (ref "Q5") (pin "G") (pinfunction "G_G") (pintype "passive"))
      (node (ref "R20") (pin "1") (pinfunction "1_1") (pintype "passive"))
    )
    (net (code "49") (name "Net-(Q6-PadG)") (class "Default")
      (node (ref "Q6") (pin "G") (pinfunction "G_G") (pintype "passive"))
      (node (ref "R21") (pin "1") (pinfunction "1_1") (pintype "passive"))
    )
    (net (code "50") (name "Net-(U2-AVDD)") (class "Default")
      (node (ref "C11") (pin "1") (pinfunction "1_1") (pintype "passive"))
      (node (ref "U2") (pin "27") (pinfunction "AVDD_27") (pintype "bidirectional"))
    )
    (net (code "51") (name "Net-(U2-BST_A)") (class "Default")
      (node (ref "C17") (pin "1") (pinfunction "1_1") (pintype "passive"))
      (node (ref "U2") (pin "48") (pinfunction "BST_A_48") (pintype "bidirectional"))
    )
    (net (code "52") (name "Net-(U2-BST_B)") (class "Default")
      (node (ref "C18") (pin "1") (pinfunction "1_1") (pintype "passive"))
      (node (ref "U2") (pin "43") (pinfunction "BST_B_43") (pintype "bidirectional"))
    )
    (net (code "53") (name "Net-(U2-BST_BK)") (class "Default")
      (node (ref "C15") (pin "1") (pinfunction "1_1") (pintype "passive"))
      (node (ref "U2") (pin "52") (pinfunction "BST_BK_52") (pintype "bidirectional"))
    )
    (net (code "54") (name "Net-(U2-BST_C)") (class "Default")
      (node (ref "C19") (pin "1") (pinfunction "1_1") (pintype "passive"))
      (node (ref "U2") (pin "38") (pinfunction "BST_C_38") (pintype "bidirectional"))
    )
    (net (code "55") (name "Net-(U2-COMP)") (class "Default")
      (node (ref "C29") (pin "2") (pinfunction "2_2") (pintype "passive"))
      (node (ref "R7") (pin "2") (pinfunction "2_2") (pintype "passive"))
      (node (ref "U2") (pin "2") (pinfunction "COMP_2") (pintype "bidirectional"))
    )
    (net (code "56") (name "Net-(U2-CP1)") (class "Default")
      (node (ref "C9") (pin "1") (pinfunction "1_1") (pintype "passive"))
      (node (ref "U2") (pin "14") (pinfunction "CP1_14") (pintype "bidirectional"))
    )
    (net (code "57") (name "Net-(U2-CP2)") (class "Default")
      (node (ref "C9") (pin "2") (pinfunction "2_2") (pintype "passive"))
      (node (ref "U2") (pin "15") (pinfunction "CP2_15") (pintype "bidirectional"))
    )
    (net (code "58") (name "Net-(U2-DVDD)") (class "Default")
      (node (ref "C10") (pin "1") (pinfunction "1_1") (pintype "passive"))
      (node (ref "U2") (pin "23") (pinfunction "DVDD_23") (pintype "bidirectional"))
    )
    (net (code "59") (name "Net-(U2-GVDD)") (class "Default")
      (node (ref "C8") (pin "1") (pinfunction "1_1") (pintype "passive"))
      (node (ref "U2") (pin "13") (pinfunction "GVDD_13") (pintype "bidirectional"))
    )
    (net (code "60") (name "Net-(U2-PH_1)") (class "Default")
      (node (ref "C15") (pin "2") (pinfunction "2_2") (pintype "passive"))
      (node (ref "D1") (pin "C") (pinfunction "C_C") (pintype "passive"))
      (node (ref "L1") (pin "1") (pinfunction "1_1") (pintype "passive"))
      (node (ref "U2") (pin "50") (pinfunction "PH_1_50") (pintype "bidirectional"))
      (node (ref "U2") (pin "51") (pinfunction "PH_2_51") (pintype "bidirectional"))
    )
    (net (code "61") (name "Net-(U2-RT_CLK)") (class "Default")
      (node (ref "R8") (pin "2") (pinfunction "2_2") (pintype "passive"))
      (node (ref "U2") (pin "1") (pinfunction "RT_CLK_1") (pintype "bidirectional"))
    )
    (net (code "62") (name "Net-(U2-SS_TR)") (class "Default")
      (node (ref "C12") (pin "2") (pinfunction "2_2") (pintype "passive"))
      (node (ref "U2") (pin "56") (pinfunction "SS_TR_56") (pintype "bidirectional"))
    )
    (net (code "63") (name "Net-(U2-VSENSE)") (class "Default")
      (node (ref "R3") (pin "1") (pinfunction "1_1") (pintype "passive"))
      (node (ref "R9") (pin "2") (pinfunction "2_2") (pintype "passive"))
      (node (ref "U2") (pin "3") (pinfunction "VSENSE_3") (pintype "bidirectional"))
    )
    (net (code "64") (name "VCC") (class "Default")
      (node (ref "C16") (pin "1") (pinfunction "1_1") (pintype "passive"))
      (node (ref "C22") (pin "1") (pinfunction "1_1") (pintype "passive"))
      (node (ref "C27") (pin "1") (pinfunction "1_1") (pintype "passive"))
      (node (ref "C35") (pin "1") (pinfunction "1_1") (pintype "passive"))
      (node (ref "C36") (pin "1") (pinfunction "1_1") (pintype "passive"))
      (node (ref "C37") (pin "1") (pinfunction "1_1") (pintype "passive"))
      (node (ref "C38") (pin "1") (pinfunction "1_1") (pintype "passive"))
      (node (ref "JP1") (pin "2") (pinfunction "2_2") (pintype "passive"))
      (node (ref "JP2") (pin "4") (pinfunction "4_4") (pintype "passive"))
      (node (ref "JP3") (pin "3") (pinfunction "3_3") (pintype "passive"))
      (node (ref "L1") (pin "2") (pinfunction "2_2") (pintype "passive"))
      (node (ref "R17") (pin "2") (pinfunction "2_2") (pintype "passive"))
      (node (ref "R18") (pin "2") (pinfunction "2_2") (pintype "passive"))
      (node (ref "R22") (pin "2") (pinfunction "2_2") (pintype "passive"))
      (node (ref "R23") (pin "2") (pinfunction "2_2") (pintype "passive"))
      (node (ref "R24") (pin "2") (pinfunction "2_2") (pintype "passive"))
      (node (ref "R3") (pin "2") (pinfunction "2_2") (pintype "passive"))
      (node (ref "R4") (pin "2") (pinfunction "2_2") (pintype "passive"))
      (node (ref "U1") (pin "VIN") (pinfunction "VIN_VIN") (pintype "power_in"))
      (node (ref "U3") (pin "1") (pinfunction "IN_1") (pintype "input"))
    )
    (net (code "65") (name "VDD") (class "Default")
      (node (ref "C1") (pin "1") (pinfunction "1_1") (pintype "passive"))
      (node (ref "C13") (pin "2") (pinfunction "2_2") (pintype "passive"))
      (node (ref "C14") (pin "1") (pinfunction "1_1") (pintype "passive"))
      (node (ref "C2") (pin "1") (pinfunction "1_1") (pintype "passive"))
      (node (ref "C20") (pin "1") (pinfunction "1_1") (pintype "passive"))
      (node (ref "C21") (pin "1") (pinfunction "1_1") (pintype "passive"))
      (node (ref "C24") (pin "1") (pinfunction "1_1") (pintype "passive"))
      (node (ref "C26") (pin "1") (pinfunction "1_1") (pintype "passive"))
      (node (ref "C28") (pin "1") (pinfunction "1_1") (pintype "passive"))
      (node (ref "C3") (pin "1") (pinfunction "1_1") (pintype "passive"))
      (node (ref "C31") (pin "+") (pinfunction "+_+") (pintype "passive"))
      (node (ref "C32") (pin "+") (pinfunction "+_+") (pintype "passive"))
      (node (ref "C33") (pin "+") (pinfunction "+_+") (pintype "passive"))
      (node (ref "C34") (pin "+") (pinfunction "+_+") (pintype "passive"))
      (node (ref "C4") (pin "1") (pinfunction "1_1") (pintype "passive"))
      (node (ref "C5") (pin "1") (pinfunction "1_1") (pintype "passive"))
      (node (ref "C6") (pin "1") (pinfunction "1_1") (pintype "passive"))
      (node (ref "C7") (pin "1") (pinfunction "1_1") (pintype "passive"))
      (node (ref "D2") (pin "C") (pinfunction "C_C") (pintype "passive"))
      (node (ref "J1") (pin "1") (pinfunction "1_1") (pintype "bidirectional"))
      (node (ref "Q1") (pin "D") (pinfunction "D_D") (pintype "passive"))
      (node (ref "Q3") (pin "D") (pinfunction "D_D") (pintype "passive"))
      (node (ref "Q5") (pin "D") (pinfunction "D_D") (pintype "passive"))
      (node (ref "R1") (pin "2") (pinfunction "2_2") (pintype "passive"))
      (node (ref "U2") (pin "29") (pinfunction "PVDD1_29") (pintype "bidirectional"))
      (node (ref "U2") (pin "53") (pinfunction "PVDD2_1_53") (pintype "bidirectional"))
      (node (ref "U2") (pin "54") (pinfunction "PVDD2_2_54") (pintype "bidirectional"))
    )
    (net (code "66") (name "unconnected-(U1-Pad3)") (class "Default")
      (node (ref "U1") (pin "3") (pinfunction "3_3") (pintype "bidirectional"))
    )
    (net (code "67") (name "unconnected-(U1-Pad21{slash}A7)") (class "Default")
      (node (ref "U1") (pin "21/A7") (pinfunction "21/A7_21/A7") (pintype "bidirectional"))
    )
    (net (code "68") (name "unconnected-(U1-Pad22{slash}A8)") (class "Default")
      (node (ref "U1") (pin "22/A8") (pinfunction "22/A8_22/A8") (pintype "bidirectional"))
    )
    (net (code "69") (name "unconnected-(U1-PadA10)") (class "Default")
      (node (ref "U1") (pin "A10") (pinfunction "A10_A10") (pintype "bidirectional"))
    )
    (net (code "70") (name "unconnected-(U1-PadA11)") (class "Default")
      (node (ref "U1") (pin "A11") (pinfunction "A11_A11") (pintype "bidirectional"))
    )
    (net (code "71") (name "unconnected-(U1-PadPGM)") (class "Default")
      (node (ref "U1") (pin "PGM") (pinfunction "PGM_PGM") (pintype "bidirectional"))
    )
    (net (code "72") (name "unconnected-(U1-PadRESET)") (class "Default")
      (node (ref "U1") (pin "RESET") (pinfunction "RESET_RESET") (pintype "bidirectional"))
    )
    (net (code "73") (name "unconnected-(U1-PadVUSB)") (class "Default")
      (node (ref "U1") (pin "VUSB") (pinfunction "VUSB_VUSB") (pintype "power_in"))
    )
    (net (code "74") (name "unconnected-(U2-EN_BUCK-Pad55)") (class "Default")
      (node (ref "U2") (pin "55") (pinfunction "EN_BUCK_55") (pintype "bidirectional"))
    )
    (net (code "75") (name "unconnected-(U2-PWRGD-Pad4)") (class "Default")
      (node (ref "U2") (pin "4") (pinfunction "PWRGD_4") (pintype "bidirectional"))
    )
    (net (code "76") (name "unconnected-(U2-SN2-Pad31)") (class "Default")
      (node (ref "U2") (pin "31") (pinfunction "SN2_31") (pintype "bidirectional"))
    )
    (net (code "77") (name "unconnected-(U2-SP2-Pad30)") (class "Default")
      (node (ref "U2") (pin "30") (pinfunction "SP2_30") (pintype "bidirectional"))
    )
    (net (code "78") (name "unconnected-(U2-{slash}OCTW-Pad5)") (class "Default")
      (node (ref "U2") (pin "5") (pinfunction "/OCTW_5") (pintype "bidirectional"))
    )
  )
)
